# Debug_Phantom_V2.net
KiCad netlist of a schematic drawn in EAGLE
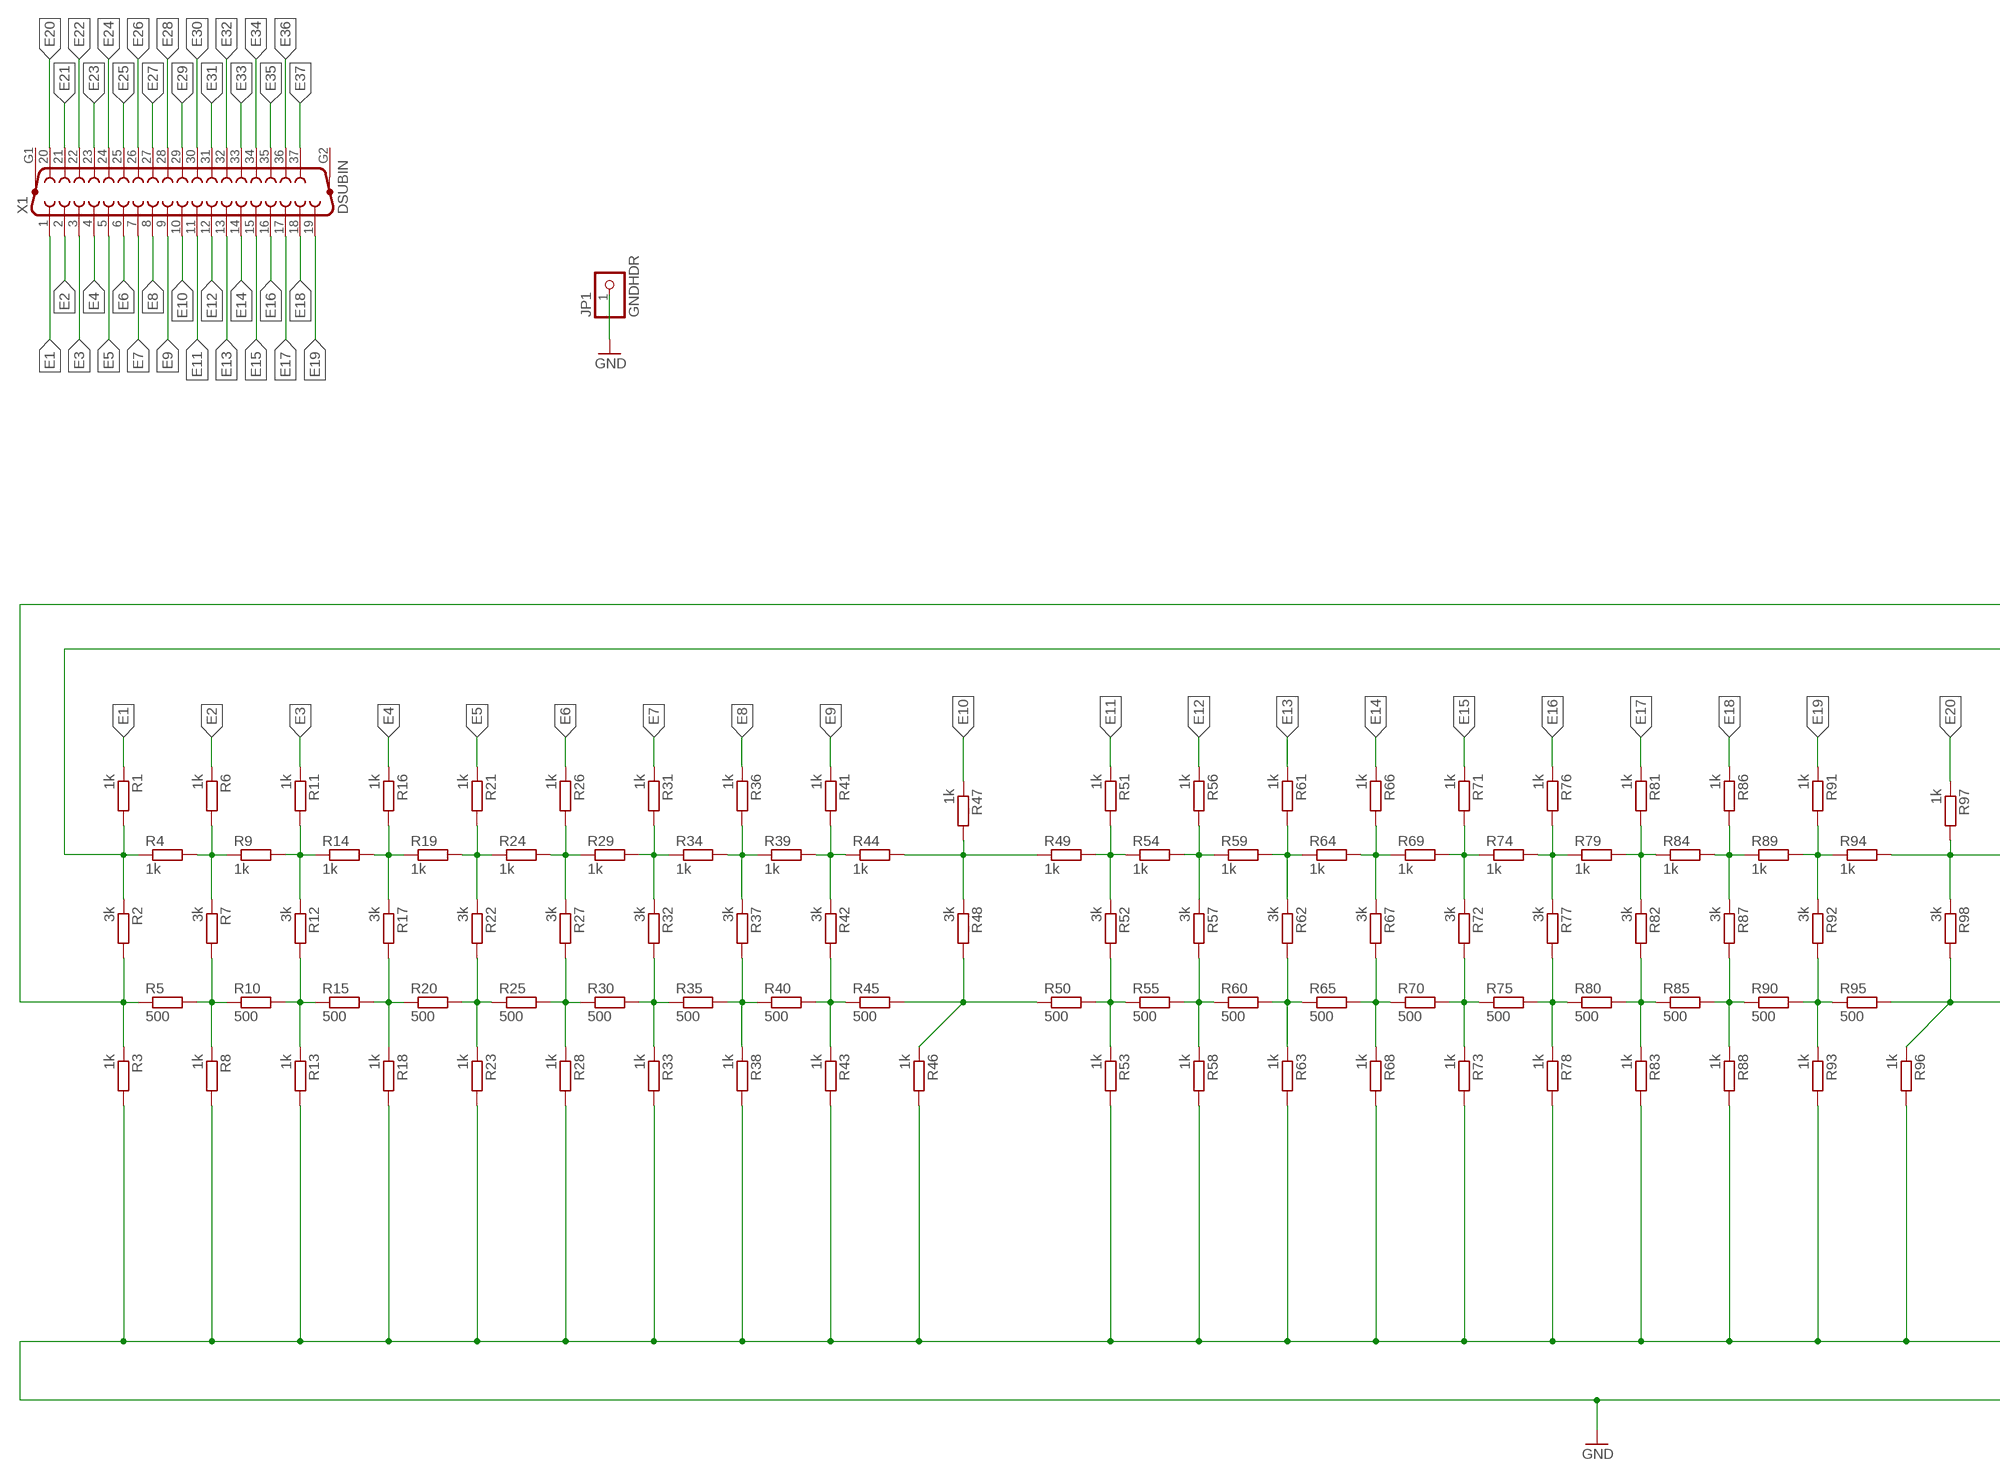
[diagram p0: schematic, sheet 1, part 1 of 2]
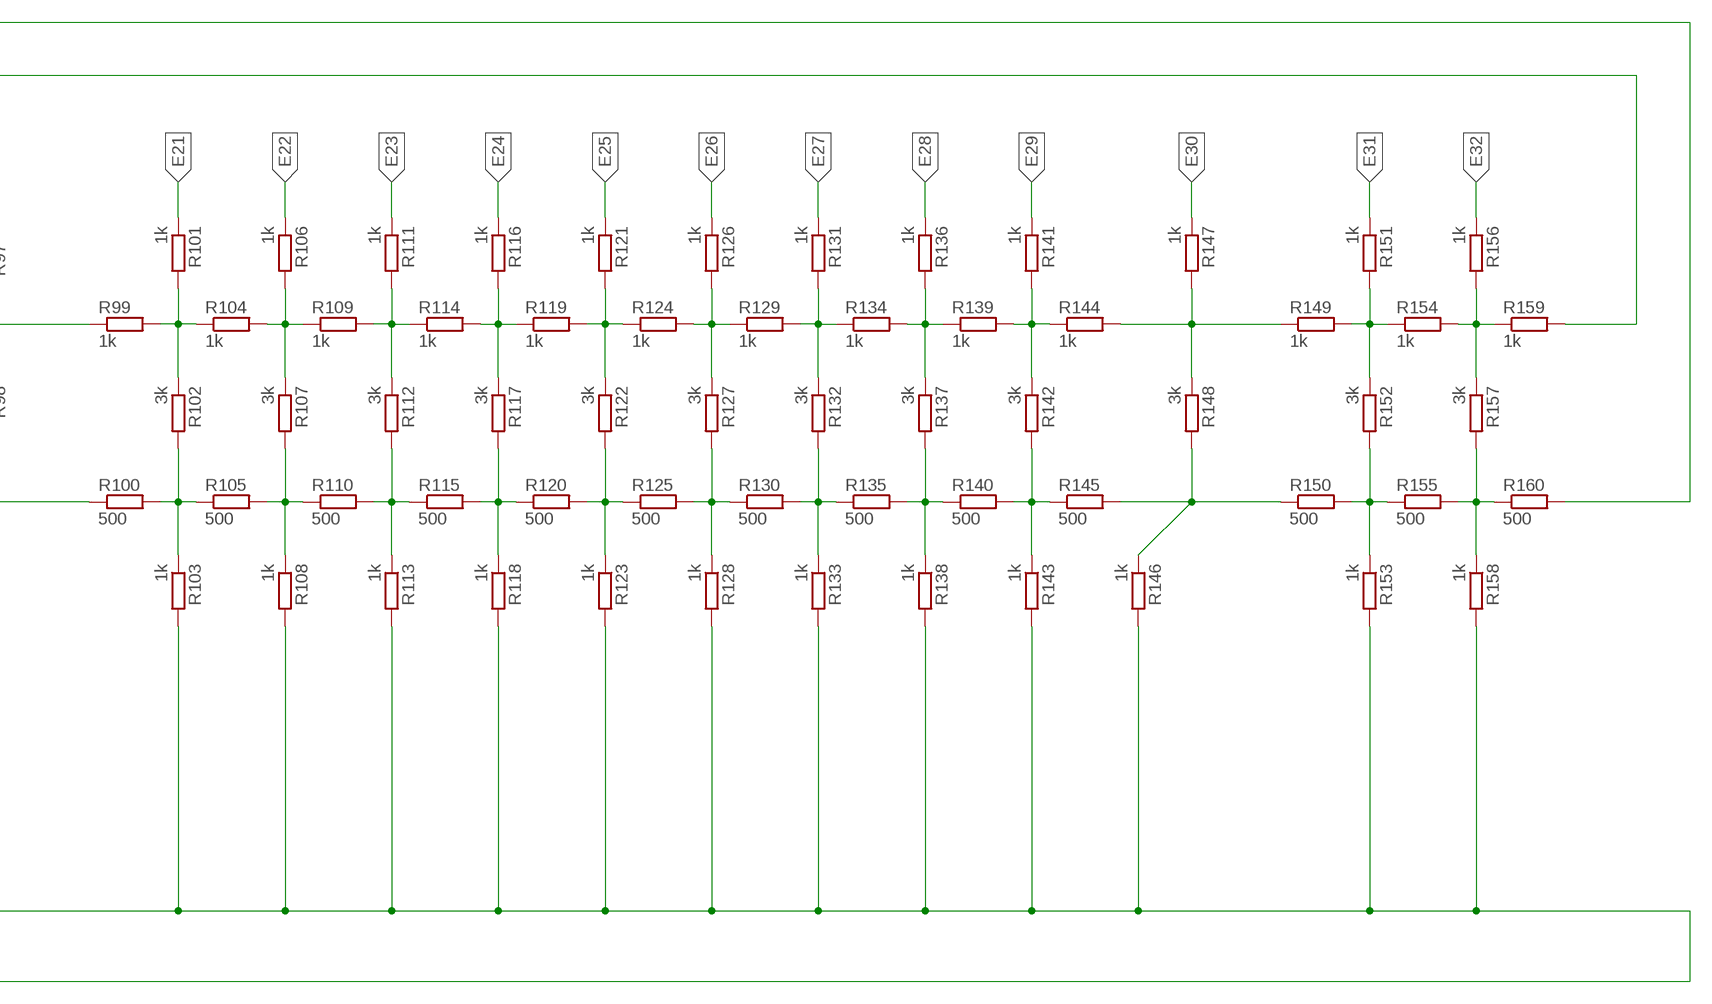
[diagram p1: schematic, sheet 1, part 2 of 2]

(export (version "E")
  (design (tool "Eeschema 10.0.6"))
  (components
    (comp (ref "JP1")
      (value "GNDHDR")
      (footprint "eagle-import:1X01")
      (libsource (lib "eagle-import") (part "PINHD-1X1"))
    )
    (comp (ref "R1")
      (value "1k")
      (footprint "eagle-import:R0402")
      (libsource (lib "eagle-import") (part "R-EU_R0402"))
    )
    (comp (ref "R2")
      (value "3k")
      (footprint "eagle-import:R0402")
      (libsource (lib "eagle-import") (part "R-EU_R0402"))
    )
    (comp (ref "R3")
      (value "1k")
      (footprint "eagle-import:R0402")
      (libsource (lib "eagle-import") (part "R-EU_R0402"))
    )
    (comp (ref "R4")
      (value "1k")
      (footprint "eagle-import:R0402")
      (libsource (lib "eagle-import") (part "R-EU_R0402"))
    )
    (comp (ref "R5")
      (value "500")
      (footprint "eagle-import:R0402")
      (libsource (lib "eagle-import") (part "R-EU_R0402"))
    )
    (comp (ref "R6")
      (value "1k")
      (footprint "eagle-import:R0402")
      (libsource (lib "eagle-import") (part "R-EU_R0402"))
    )
    (comp (ref "R7")
      (value "3k")
      (footprint "eagle-import:R0402")
      (libsource (lib "eagle-import") (part "R-EU_R0402"))
    )
    (comp (ref "R8")
      (value "1k")
      (footprint "eagle-import:R0402")
      (libsource (lib "eagle-import") (part "R-EU_R0402"))
    )
    (comp (ref "R9")
      (value "1k")
      (footprint "eagle-import:R0402")
      (libsource (lib "eagle-import") (part "R-EU_R0402"))
    )
    (comp (ref "R10")
      (value "500")
      (footprint "eagle-import:R0402")
      (libsource (lib "eagle-import") (part "R-EU_R0402"))
    )
    (comp (ref "R11")
      (value "1k")
      (footprint "eagle-import:R0402")
      (libsource (lib "eagle-import") (part "R-EU_R0402"))
    )
    (comp (ref "R12")
      (value "3k")
      (footprint "eagle-import:R0402")
      (libsource (lib "eagle-import") (part "R-EU_R0402"))
    )
    (comp (ref "R13")
      (value "1k")
      (footprint "eagle-import:R0402")
      (libsource (lib "eagle-import") (part "R-EU_R0402"))
    )
    (comp (ref "R14")
      (value "1k")
      (footprint "eagle-import:R0402")
      (libsource (lib "eagle-import") (part "R-EU_R0402"))
    )
    (comp (ref "R15")
      (value "500")
      (footprint "eagle-import:R0402")
      (libsource (lib "eagle-import") (part "R-EU_R0402"))
    )
    (comp (ref "R16")
      (value "1k")
      (footprint "eagle-import:R0402")
      (libsource (lib "eagle-import") (part "R-EU_R0402"))
    )
    (comp (ref "R17")
      (value "3k")
      (footprint "eagle-import:R0402")
      (libsource (lib "eagle-import") (part "R-EU_R0402"))
    )
    (comp (ref "R18")
      (value "1k")
      (footprint "eagle-import:R0402")
      (libsource (lib "eagle-import") (part "R-EU_R0402"))
    )
    (comp (ref "R19")
      (value "1k")
      (footprint "eagle-import:R0402")
      (libsource (lib "eagle-import") (part "R-EU_R0402"))
    )
    (comp (ref "R20")
      (value "500")
      (footprint "eagle-import:R0402")
      (libsource (lib "eagle-import") (part "R-EU_R0402"))
    )
    (comp (ref "R21")
      (value "1k")
      (footprint "eagle-import:R0402")
      (libsource (lib "eagle-import") (part "R-EU_R0402"))
    )
    (comp (ref "R22")
      (value "3k")
      (footprint "eagle-import:R0402")
      (libsource (lib "eagle-import") (part "R-EU_R0402"))
    )
    (comp (ref "R23")
      (value "1k")
      (footprint "eagle-import:R0402")
      (libsource (lib "eagle-import") (part "R-EU_R0402"))
    )
    (comp (ref "R24")
      (value "1k")
      (footprint "eagle-import:R0402")
      (libsource (lib "eagle-import") (part "R-EU_R0402"))
    )
    (comp (ref "R25")
      (value "500")
      (footprint "eagle-import:R0402")
      (libsource (lib "eagle-import") (part "R-EU_R0402"))
    )
    (comp (ref "R26")
      (value "1k")
      (footprint "eagle-import:R0402")
      (libsource (lib "eagle-import") (part "R-EU_R0402"))
    )
    (comp (ref "R27")
      (value "3k")
      (footprint "eagle-import:R0402")
      (libsource (lib "eagle-import") (part "R-EU_R0402"))
    )
    (comp (ref "R28")
      (value "1k")
      (footprint "eagle-import:R0402")
      (libsource (lib "eagle-import") (part "R-EU_R0402"))
    )
    (comp (ref "R29")
      (value "1k")
      (footprint "eagle-import:R0402")
      (libsource (lib "eagle-import") (part "R-EU_R0402"))
    )
    (comp (ref "R30")
      (value "500")
      (footprint "eagle-import:R0402")
      (libsource (lib "eagle-import") (part "R-EU_R0402"))
    )
    (comp (ref "R31")
      (value "1k")
      (footprint "eagle-import:R0402")
      (libsource (lib "eagle-import") (part "R-EU_R0402"))
    )
    (comp (ref "R32")
      (value "3k")
      (footprint "eagle-import:R0402")
      (libsource (lib "eagle-import") (part "R-EU_R0402"))
    )
    (comp (ref "R33")
      (value "1k")
      (footprint "eagle-import:R0402")
      (libsource (lib "eagle-import") (part "R-EU_R0402"))
    )
    (comp (ref "R34")
      (value "1k")
      (footprint "eagle-import:R0402")
      (libsource (lib "eagle-import") (part "R-EU_R0402"))
    )
    (comp (ref "R35")
      (value "500")
      (footprint "eagle-import:R0402")
      (libsource (lib "eagle-import") (part "R-EU_R0402"))
    )
    (comp (ref "R36")
      (value "1k")
      (footprint "eagle-import:R0402")
      (libsource (lib "eagle-import") (part "R-EU_R0402"))
    )
    (comp (ref "R37")
      (value "3k")
      (footprint "eagle-import:R0402")
      (libsource (lib "eagle-import") (part "R-EU_R0402"))
    )
    (comp (ref "R38")
      (value "1k")
      (footprint "eagle-import:R0402")
      (libsource (lib "eagle-import") (part "R-EU_R0402"))
    )
    (comp (ref "R39")
      (value "1k")
      (footprint "eagle-import:R0402")
      (libsource (lib "eagle-import") (part "R-EU_R0402"))
    )
    (comp (ref "R40")
      (value "500")
      (footprint "eagle-import:R0402")
      (libsource (lib "eagle-import") (part "R-EU_R0402"))
    )
    (comp (ref "R41")
      (value "1k")
      (footprint "eagle-import:R0402")
      (libsource (lib "eagle-import") (part "R-EU_R0402"))
    )
    (comp (ref "R42")
      (value "3k")
      (footprint "eagle-import:R0402")
      (libsource (lib "eagle-import") (part "R-EU_R0402"))
    )
    (comp (ref "R43")
      (value "1k")
      (footprint "eagle-import:R0402")
      (libsource (lib "eagle-import") (part "R-EU_R0402"))
    )
    (comp (ref "R44")
      (value "1k")
      (footprint "eagle-import:R0402")
      (libsource (lib "eagle-import") (part "R-EU_R0402"))
    )
    (comp (ref "R45")
      (value "500")
      (footprint "eagle-import:R0402")
      (libsource (lib "eagle-import") (part "R-EU_R0402"))
    )
    (comp (ref "R46")
      (value "1k")
      (footprint "eagle-import:R0402")
      (libsource (lib "eagle-import") (part "R-EU_R0402"))
    )
    (comp (ref "R47")
      (value "1k")
      (footprint "eagle-import:R0402")
      (libsource (lib "eagle-import") (part "R-EU_R0402"))
    )
    (comp (ref "R48")
      (value "3k")
      (footprint "eagle-import:R0402")
      (libsource (lib "eagle-import") (part "R-EU_R0402"))
    )
    (comp (ref "R49")
      (value "1k")
      (footprint "eagle-import:R0402")
      (libsource (lib "eagle-import") (part "R-EU_R0402"))
    )
    (comp (ref "R50")
      (value "500")
      (footprint "eagle-import:R0402")
      (libsource (lib "eagle-import") (part "R-EU_R0402"))
    )
    (comp (ref "R51")
      (value "1k")
      (footprint "eagle-import:R0402")
      (libsource (lib "eagle-import") (part "R-EU_R0402"))
    )
    (comp (ref "R52")
      (value "3k")
      (footprint "eagle-import:R0402")
      (libsource (lib "eagle-import") (part "R-EU_R0402"))
    )
    (comp (ref "R53")
      (value "1k")
      (footprint "eagle-import:R0402")
      (libsource (lib "eagle-import") (part "R-EU_R0402"))
    )
    (comp (ref "R54")
      (value "1k")
      (footprint "eagle-import:R0402")
      (libsource (lib "eagle-import") (part "R-EU_R0402"))
    )
    (comp (ref "R55")
      (value "500")
      (footprint "eagle-import:R0402")
      (libsource (lib "eagle-import") (part "R-EU_R0402"))
    )
    (comp (ref "R56")
      (value "1k")
      (footprint "eagle-import:R0402")
      (libsource (lib "eagle-import") (part "R-EU_R0402"))
    )
    (comp (ref "R57")
      (value "3k")
      (footprint "eagle-import:R0402")
      (libsource (lib "eagle-import") (part "R-EU_R0402"))
    )
    (comp (ref "R58")
      (value "1k")
      (footprint "eagle-import:R0402")
      (libsource (lib "eagle-import") (part "R-EU_R0402"))
    )
    (comp (ref "R59")
      (value "1k")
      (footprint "eagle-import:R0402")
      (libsource (lib "eagle-import") (part "R-EU_R0402"))
    )
    (comp (ref "R60")
      (value "500")
      (footprint "eagle-import:R0402")
      (libsource (lib "eagle-import") (part "R-EU_R0402"))
    )
    (comp (ref "R61")
      (value "1k")
      (footprint "eagle-import:R0402")
      (libsource (lib "eagle-import") (part "R-EU_R0402"))
    )
    (comp (ref "R62")
      (value "3k")
      (footprint "eagle-import:R0402")
      (libsource (lib "eagle-import") (part "R-EU_R0402"))
    )
    (comp (ref "R63")
      (value "1k")
      (footprint "eagle-import:R0402")
      (libsource (lib "eagle-import") (part "R-EU_R0402"))
    )
    (comp (ref "R64")
      (value "1k")
      (footprint "eagle-import:R0402")
      (libsource (lib "eagle-import") (part "R-EU_R0402"))
    )
    (comp (ref "R65")
      (value "500")
      (footprint "eagle-import:R0402")
      (libsource (lib "eagle-import") (part "R-EU_R0402"))
    )
    (comp (ref "R66")
      (value "1k")
      (footprint "eagle-import:R0402")
      (libsource (lib "eagle-import") (part "R-EU_R0402"))
    )
    (comp (ref "R67")
      (value "3k")
      (footprint "eagle-import:R0402")
      (libsource (lib "eagle-import") (part "R-EU_R0402"))
    )
    (comp (ref "R68")
      (value "1k")
      (footprint "eagle-import:R0402")
      (libsource (lib "eagle-import") (part "R-EU_R0402"))
    )
    (comp (ref "R69")
      (value "1k")
      (footprint "eagle-import:R0402")
      (libsource (lib "eagle-import") (part "R-EU_R0402"))
    )
    (comp (ref "R70")
      (value "500")
      (footprint "eagle-import:R0402")
      (libsource (lib "eagle-import") (part "R-EU_R0402"))
    )
    (comp (ref "R71")
      (value "1k")
      (footprint "eagle-import:R0402")
      (libsource (lib "eagle-import") (part "R-EU_R0402"))
    )
    (comp (ref "R72")
      (value "3k")
      (footprint "eagle-import:R0402")
      (libsource (lib "eagle-import") (part "R-EU_R0402"))
    )
    (comp (ref "R73")
      (value "1k")
      (footprint "eagle-import:R0402")
      (libsource (lib "eagle-import") (part "R-EU_R0402"))
    )
    (comp (ref "R74")
      (value "1k")
      (footprint "eagle-import:R0402")
      (libsource (lib "eagle-import") (part "R-EU_R0402"))
    )
    (comp (ref "R75")
      (value "500")
      (footprint "eagle-import:R0402")
      (libsource (lib "eagle-import") (part "R-EU_R0402"))
    )
    (comp (ref "R76")
      (value "1k")
      (footprint "eagle-import:R0402")
      (libsource (lib "eagle-import") (part "R-EU_R0402"))
    )
    (comp (ref "R77")
      (value "3k")
      (footprint "eagle-import:R0402")
      (libsource (lib "eagle-import") (part "R-EU_R0402"))
    )
    (comp (ref "R78")
      (value "1k")
      (footprint "eagle-import:R0402")
      (libsource (lib "eagle-import") (part "R-EU_R0402"))
    )
    (comp (ref "R79")
      (value "1k")
      (footprint "eagle-import:R0402")
      (libsource (lib "eagle-import") (part "R-EU_R0402"))
    )
    (comp (ref "R80")
      (value "500")
      (footprint "eagle-import:R0402")
      (libsource (lib "eagle-import") (part "R-EU_R0402"))
    )
    (comp (ref "R81")
      (value "1k")
      (footprint "eagle-import:R0402")
      (libsource (lib "eagle-import") (part "R-EU_R0402"))
    )
    (comp (ref "R82")
      (value "3k")
      (footprint "eagle-import:R0402")
      (libsource (lib "eagle-import") (part "R-EU_R0402"))
    )
    (comp (ref "R83")
      (value "1k")
      (footprint "eagle-import:R0402")
      (libsource (lib "eagle-import") (part "R-EU_R0402"))
    )
    (comp (ref "R84")
      (value "1k")
      (footprint "eagle-import:R0402")
      (libsource (lib "eagle-import") (part "R-EU_R0402"))
    )
    (comp (ref "R85")
      (value "500")
      (footprint "eagle-import:R0402")
      (libsource (lib "eagle-import") (part "R-EU_R0402"))
    )
    (comp (ref "R86")
      (value "1k")
      (footprint "eagle-import:R0402")
      (libsource (lib "eagle-import") (part "R-EU_R0402"))
    )
    (comp (ref "R87")
      (value "3k")
      (footprint "eagle-import:R0402")
      (libsource (lib "eagle-import") (part "R-EU_R0402"))
    )
    (comp (ref "R88")
      (value "1k")
      (footprint "eagle-import:R0402")
      (libsource (lib "eagle-import") (part "R-EU_R0402"))
    )
    (comp (ref "R89")
      (value "1k")
      (footprint "eagle-import:R0402")
      (libsource (lib "eagle-import") (part "R-EU_R0402"))
    )
    (comp (ref "R90")
      (value "500")
      (footprint "eagle-import:R0402")
      (libsource (lib "eagle-import") (part "R-EU_R0402"))
    )
    (comp (ref "R91")
      (value "1k")
      (footprint "eagle-import:R0402")
      (libsource (lib "eagle-import") (part "R-EU_R0402"))
    )
    (comp (ref "R92")
      (value "3k")
      (footprint "eagle-import:R0402")
      (libsource (lib "eagle-import") (part "R-EU_R0402"))
    )
    (comp (ref "R93")
      (value "1k")
      (footprint "eagle-import:R0402")
      (libsource (lib "eagle-import") (part "R-EU_R0402"))
    )
    (comp (ref "R94")
      (value "1k")
      (footprint "eagle-import:R0402")
      (libsource (lib "eagle-import") (part "R-EU_R0402"))
    )
    (comp (ref "R95")
      (value "500")
      (footprint "eagle-import:R0402")
      (libsource (lib "eagle-import") (part "R-EU_R0402"))
    )
    (comp (ref "R96")
      (value "1k")
      (footprint "eagle-import:R0402")
      (libsource (lib "eagle-import") (part "R-EU_R0402"))
    )
    (comp (ref "R97")
      (value "1k")
      (footprint "eagle-import:R0402")
      (libsource (lib "eagle-import") (part "R-EU_R0402"))
    )
    (comp (ref "R98")
      (value "3k")
      (footprint "eagle-import:R0402")
      (libsource (lib "eagle-import") (part "R-EU_R0402"))
    )
    (comp (ref "R99")
      (value "1k")
      (footprint "eagle-import:R0402")
      (libsource (lib "eagle-import") (part "R-EU_R0402"))
    )
    (comp (ref "R100")
      (value "500")
      (footprint "eagle-import:R0402")
      (libsource (lib "eagle-import") (part "R-EU_R0402"))
    )
    (comp (ref "R101")
      (value "1k")
      (footprint "eagle-import:R0402")
      (libsource (lib "eagle-import") (part "R-EU_R0402"))
    )
    (comp (ref "R102")
      (value "3k")
      (footprint "eagle-import:R0402")
      (libsource (lib "eagle-import") (part "R-EU_R0402"))
    )
    (comp (ref "R103")
      (value "1k")
      (footprint "eagle-import:R0402")
      (libsource (lib "eagle-import") (part "R-EU_R0402"))
    )
    (comp (ref "R104")
      (value "1k")
      (footprint "eagle-import:R0402")
      (libsource (lib "eagle-import") (part "R-EU_R0402"))
    )
    (comp (ref "R105")
      (value "500")
      (footprint "eagle-import:R0402")
      (libsource (lib "eagle-import") (part "R-EU_R0402"))
    )
    (comp (ref "R106")
      (value "1k")
      (footprint "eagle-import:R0402")
      (libsource (lib "eagle-import") (part "R-EU_R0402"))
    )
    (comp (ref "R107")
      (value "3k")
      (footprint "eagle-import:R0402")
      (libsource (lib "eagle-import") (part "R-EU_R0402"))
    )
    (comp (ref "R108")
      (value "1k")
      (footprint "eagle-import:R0402")
      (libsource (lib "eagle-import") (part "R-EU_R0402"))
    )
    (comp (ref "R109")
      (value "1k")
      (footprint "eagle-import:R0402")
      (libsource (lib "eagle-import") (part "R-EU_R0402"))
    )
    (comp (ref "R110")
      (value "500")
      (footprint "eagle-import:R0402")
      (libsource (lib "eagle-import") (part "R-EU_R0402"))
    )
    (comp (ref "R111")
      (value "1k")
      (footprint "eagle-import:R0402")
      (libsource (lib "eagle-import") (part "R-EU_R0402"))
    )
    (comp (ref "R112")
      (value "3k")
      (footprint "eagle-import:R0402")
      (libsource (lib "eagle-import") (part "R-EU_R0402"))
    )
    (comp (ref "R113")
      (value "1k")
      (footprint "eagle-import:R0402")
      (libsource (lib "eagle-import") (part "R-EU_R0402"))
    )
    (comp (ref "R114")
      (value "1k")
      (footprint "eagle-import:R0402")
      (libsource (lib "eagle-import") (part "R-EU_R0402"))
    )
    (comp (ref "R115")
      (value "500")
      (footprint "eagle-import:R0402")
      (libsource (lib "eagle-import") (part "R-EU_R0402"))
    )
    (comp (ref "R116")
      (value "1k")
      (footprint "eagle-import:R0402")
      (libsource (lib "eagle-import") (part "R-EU_R0402"))
    )
    (comp (ref "R117")
      (value "3k")
      (footprint "eagle-import:R0402")
      (libsource (lib "eagle-import") (part "R-EU_R0402"))
    )
    (comp (ref "R118")
      (value "1k")
      (footprint "eagle-import:R0402")
      (libsource (lib "eagle-import") (part "R-EU_R0402"))
    )
    (comp (ref "R119")
      (value "1k")
      (footprint "eagle-import:R0402")
      (libsource (lib "eagle-import") (part "R-EU_R0402"))
    )
    (comp (ref "R120")
      (value "500")
      (footprint "eagle-import:R0402")
      (libsource (lib "eagle-import") (part "R-EU_R0402"))
    )
    (comp (ref "R121")
      (value "1k")
      (footprint "eagle-import:R0402")
      (libsource (lib "eagle-import") (part "R-EU_R0402"))
    )
    (comp (ref "R122")
      (value "3k")
      (footprint "eagle-import:R0402")
      (libsource (lib "eagle-import") (part "R-EU_R0402"))
    )
    (comp (ref "R123")
      (value "1k")
      (footprint "eagle-import:R0402")
      (libsource (lib "eagle-import") (part "R-EU_R0402"))
    )
    (comp (ref "R124")
      (value "1k")
      (footprint "eagle-import:R0402")
      (libsource (lib "eagle-import") (part "R-EU_R0402"))
    )
    (comp (ref "R125")
      (value "500")
      (footprint "eagle-import:R0402")
      (libsource (lib "eagle-import") (part "R-EU_R0402"))
    )
    (comp (ref "R126")
      (value "1k")
      (footprint "eagle-import:R0402")
      (libsource (lib "eagle-import") (part "R-EU_R0402"))
    )
    (comp (ref "R127")
      (value "3k")
      (footprint "eagle-import:R0402")
      (libsource (lib "eagle-import") (part "R-EU_R0402"))
    )
    (comp (ref "R128")
      (value "1k")
      (footprint "eagle-import:R0402")
      (libsource (lib "eagle-import") (part "R-EU_R0402"))
    )
    (comp (ref "R129")
      (value "1k")
      (footprint "eagle-import:R0402")
      (libsource (lib "eagle-import") (part "R-EU_R0402"))
    )
    (comp (ref "R130")
      (value "500")
      (footprint "eagle-import:R0402")
      (libsource (lib "eagle-import") (part "R-EU_R0402"))
    )
    (comp (ref "R131")
      (value "1k")
      (footprint "eagle-import:R0402")
      (libsource (lib "eagle-import") (part "R-EU_R0402"))
    )
    (comp (ref "R132")
      (value "3k")
      (footprint "eagle-import:R0402")
      (libsource (lib "eagle-import") (part "R-EU_R0402"))
    )
    (comp (ref "R133")
      (value "1k")
      (footprint "eagle-import:R0402")
      (libsource (lib "eagle-import") (part "R-EU_R0402"))
    )
    (comp (ref "R134")
      (value "1k")
      (footprint "eagle-import:R0402")
      (libsource (lib "eagle-import") (part "R-EU_R0402"))
    )
    (comp (ref "R135")
      (value "500")
      (footprint "eagle-import:R0402")
      (libsource (lib "eagle-import") (part "R-EU_R0402"))
    )
    (comp (ref "R136")
      (value "1k")
      (footprint "eagle-import:R0402")
      (libsource (lib "eagle-import") (part "R-EU_R0402"))
    )
    (comp (ref "R137")
      (value "3k")
      (footprint "eagle-import:R0402")
      (libsource (lib "eagle-import") (part "R-EU_R0402"))
    )
    (comp (ref "R138")
      (value "1k")
      (footprint "eagle-import:R0402")
      (libsource (lib "eagle-import") (part "R-EU_R0402"))
    )
    (comp (ref "R139")
      (value "1k")
      (footprint "eagle-import:R0402")
      (libsource (lib "eagle-import") (part "R-EU_R0402"))
    )
    (comp (ref "R140")
      (value "500")
      (footprint "eagle-import:R0402")
      (libsource (lib "eagle-import") (part "R-EU_R0402"))
    )
    (comp (ref "R141")
      (value "1k")
      (footprint "eagle-import:R0402")
      (libsource (lib "eagle-import") (part "R-EU_R0402"))
    )
    (comp (ref "R142")
      (value "3k")
      (footprint "eagle-import:R0402")
      (libsource (lib "eagle-import") (part "R-EU_R0402"))
    )
    (comp (ref "R143")
      (value "1k")
      (footprint "eagle-import:R0402")
      (libsource (lib "eagle-import") (part "R-EU_R0402"))
    )
    (comp (ref "R144")
      (value "1k")
      (footprint "eagle-import:R0402")
      (libsource (lib "eagle-import") (part "R-EU_R0402"))
    )
    (comp (ref "R145")
      (value "500")
      (footprint "eagle-import:R0402")
      (libsource (lib "eagle-import") (part "R-EU_R0402"))
    )
    (comp (ref "R146")
      (value "1k")
      (footprint "eagle-import:R0402")
      (libsource (lib "eagle-import") (part "R-EU_R0402"))
    )
    (comp (ref "R147")
      (value "1k")
      (footprint "eagle-import:R0402")
      (libsource (lib "eagle-import") (part "R-EU_R0402"))
    )
    (comp (ref "R148")
      (value "3k")
      (footprint "eagle-import:R0402")
      (libsource (lib "eagle-import") (part "R-EU_R0402"))
    )
    (comp (ref "R149")
      (value "1k")
      (footprint "eagle-import:R0402")
      (libsource (lib "eagle-import") (part "R-EU_R0402"))
    )
    (comp (ref "R150")
      (value "500")
      (footprint "eagle-import:R0402")
      (libsource (lib "eagle-import") (part "R-EU_R0402"))
    )
    (comp (ref "R151")
      (value "1k")
      (footprint "eagle-import:R0402")
      (libsource (lib "eagle-import") (part "R-EU_R0402"))
    )
    (comp (ref "R152")
      (value "3k")
      (footprint "eagle-import:R0402")
      (libsource (lib "eagle-import") (part "R-EU_R0402"))
    )
    (comp (ref "R153")
      (value "1k")
      (footprint "eagle-import:R0402")
      (libsource (lib "eagle-import") (part "R-EU_R0402"))
    )
    (comp (ref "R154")
      (value "1k")
      (footprint "eagle-import:R0402")
      (libsource (lib "eagle-import") (part "R-EU_R0402"))
    )
    (comp (ref "R155")
      (value "500")
      (footprint "eagle-import:R0402")
      (libsource (lib "eagle-import") (part "R-EU_R0402"))
    )
    (comp (ref "R156")
      (value "1k")
      (footprint "eagle-import:R0402")
      (libsource (lib "eagle-import") (part "R-EU_R0402"))
    )
    (comp (ref "R157")
      (value "3k")
      (footprint "eagle-import:R0402")
      (libsource (lib "eagle-import") (part "R-EU_R0402"))
    )
    (comp (ref "R158")
      (value "1k")
      (footprint "eagle-import:R0402")
      (libsource (lib "eagle-import") (part "R-EU_R0402"))
    )
    (comp (ref "R159")
      (value "1k")
      (footprint "eagle-import:R0402")
      (libsource (lib "eagle-import") (part "R-EU_R0402"))
    )
    (comp (ref "R160")
      (value "500")
      (footprint "eagle-import:R0402")
      (libsource (lib "eagle-import") (part "R-EU_R0402"))
    )
    (comp (ref "X1")
      (value "DSUBIN")
      (footprint "eagle-import:F37VP")
      (libsource (lib "eagle-import") (part "F37VP"))
    )
  )
  (nets
    (net (code "1") (name "E1") (class "Default")
      (node (ref "R1") (pin "1") (pinfunction "1_1") (pintype "passive"))
      (node (ref "X1") (pin "1") (pinfunction "1_1") (pintype "passive"))
    )
    (net (code "2") (name "E2") (class "Default")
      (node (ref "R6") (pin "1") (pinfunction "1_1") (pintype "passive"))
      (node (ref "X1") (pin "2") (pinfunction "2_2") (pintype "passive"))
    )
    (net (code "3") (name "E3") (class "Default")
      (node (ref "R11") (pin "1") (pinfunction "1_1") (pintype "passive"))
      (node (ref "X1") (pin "3") (pinfunction "3_3") (pintype "passive"))
    )
    (net (code "4") (name "E4") (class "Default")
      (node (ref "R16") (pin "1") (pinfunction "1_1") (pintype "passive"))
      (node (ref "X1") (pin "4") (pinfunction "4_4") (pintype "passive"))
    )
    (net (code "5") (name "E5") (class "Default")
      (node (ref "R21") (pin "1") (pinfunction "1_1") (pintype "passive"))
      (node (ref "X1") (pin "5") (pinfunction "5_5") (pintype "passive"))
    )
    (net (code "6") (name "E6") (class "Default")
      (node (ref "R26") (pin "1") (pinfunction "1_1") (pintype "passive"))
      (node (ref "X1") (pin "6") (pinfunction "6_6") (pintype "passive"))
    )
    (net (code "7") (name "E7") (class "Default")
      (node (ref "R31") (pin "1") (pinfunction "1_1") (pintype "passive"))
      (node (ref "X1") (pin "7") (pinfunction "7_7") (pintype "passive"))
    )
    (net (code "8") (name "E8") (class "Default")
      (node (ref "R36") (pin "1") (pinfunction "1_1") (pintype "passive"))
      (node (ref "X1") (pin "8") (pinfunction "8_8") (pintype "passive"))
    )
    (net (code "9") (name "E9") (class "Default")
      (node (ref "R41") (pin "1") (pinfunction "1_1") (pintype "passive"))
      (node (ref "X1") (pin "9") (pinfunction "9_9") (pintype "passive"))
    )
    (net (code "10") (name "E10") (class "Default")
      (node (ref "R47") (pin "1") (pinfunction "1_1") (pintype "passive"))
      (node (ref "X1") (pin "10") (pinfunction "10_10") (pintype "passive"))
    )
    (net (code "11") (name "E11") (class "Default")
      (node (ref "R51") (pin "1") (pinfunction "1_1") (pintype "passive"))
      (node (ref "X1") (pin "11") (pinfunction "11_11") (pintype "passive"))
    )
    (net (code "12") (name "E12") (class "Default")
      (node (ref "R56") (pin "1") (pinfunction "1_1") (pintype "passive"))
      (node (ref "X1") (pin "12") (pinfunction "12_12") (pintype "passive"))
    )
    (net (code "13") (name "E13") (class "Default")
      (node (ref "R61") (pin "1") (pinfunction "1_1") (pintype "passive"))
      (node (ref "X1") (pin "13") (pinfunction "13_13") (pintype "passive"))
    )
    (net (code "14") (name "E14") (class "Default")
      (node (ref "R66") (pin "1") (pinfunction "1_1") (pintype "passive"))
      (node (ref "X1") (pin "14") (pinfunction "14_14") (pintype "passive"))
    )
    (net (code "15") (name "E15") (class "Default")
      (node (ref "R71") (pin "1") (pinfunction "1_1") (pintype "passive"))
      (node (ref "X1") (pin "15") (pinfunction "15_15") (pintype "passive"))
    )
    (net (code "16") (name "E16") (class "Default")
      (node (ref "R76") (pin "1") (pinfunction "1_1") (pintype "passive"))
      (node (ref "X1") (pin "16") (pinfunction "16_16") (pintype "passive"))
    )
    (net (code "17") (name "E17") (class "Default")
      (node (ref "R81") (pin "1") (pinfunction "1_1") (pintype "passive"))
      (node (ref "X1") (pin "17") (pinfunction "17_17") (pintype "passive"))
    )
    (net (code "18") (name "E18") (class "Default")
      (node (ref "R86") (pin "1") (pinfunction "1_1") (pintype "passive"))
      (node (ref "X1") (pin "18") (pinfunction "18_18") (pintype "passive"))
    )
    (net (code "19") (name "E19") (class "Default")
      (node (ref "R91") (pin "1") (pinfunction "1_1") (pintype "passive"))
      (node (ref "X1") (pin "19") (pinfunction "19_19") (pintype "passive"))
    )
    (net (code "20") (name "E20") (class "Default")
      (node (ref "R97") (pin "1") (pinfunction "1_1") (pintype "passive"))
      (node (ref "X1") (pin "20") (pinfunction "20_20") (pintype "passive"))
    )
    (net (code "21") (name "E21") (class "Default")
      (node (ref "R101") (pin "1") (pinfunction "1_1") (pintype "passive"))
      (node (ref "X1") (pin "21") (pinfunction "21_21") (pintype "passive"))
    )
    (net (code "22") (name "E22") (class "Default")
      (node (ref "R106") (pin "1") (pinfunction "1_1") (pintype "passive"))
      (node (ref "X1") (pin "22") (pinfunction "22_22") (pintype "passive"))
    )
    (net (code "23") (name "E23") (class "Default")
      (node (ref "R111") (pin "1") (pinfunction "1_1") (pintype "passive"))
      (node (ref "X1") (pin "23") (pinfunction "23_23") (pintype "passive"))
    )
    (net (code "24") (name "E24") (class "Default")
      (node (ref "R116") (pin "1") (pinfunction "1_1") (pintype "passive"))
      (node (ref "X1") (pin "24") (pinfunction "24_24") (pintype "passive"))
    )
    (net (code "25") (name "E25") (class "Default")
      (node (ref "R121") (pin "1") (pinfunction "1_1") (pintype "passive"))
      (node (ref "X1") (pin "25") (pinfunction "25_25") (pintype "passive"))
    )
    (net (code "26") (name "E26") (class "Default")
      (node (ref "R126") (pin "1") (pinfunction "1_1") (pintype "passive"))
      (node (ref "X1") (pin "26") (pinfunction "26_26") (pintype "passive"))
    )
    (net (code "27") (name "E27") (class "Default")
      (node (ref "R131") (pin "1") (pinfunction "1_1") (pintype "passive"))
      (node (ref "X1") (pin "27") (pinfunction "27_27") (pintype "passive"))
    )
    (net (code "28") (name "E28") (class "Default")
      (node (ref "R136") (pin "1") (pinfunction "1_1") (pintype "passive"))
      (node (ref "X1") (pin "28") (pinfunction "28_28") (pintype "passive"))
    )
    (net (code "29") (name "E29") (class "Default")
      (node (ref "R141") (pin "1") (pinfunction "1_1") (pintype "passive"))
      (node (ref "X1") (pin "29") (pinfunction "29_29") (pintype "passive"))
    )
    (net (code "30") (name "E30") (class "Default")
      (node (ref "R147") (pin "1") (pinfunction "1_1") (pintype "passive"))
      (node (ref "X1") (pin "30") (pinfunction "30_30") (pintype "passive"))
    )
    (net (code "31") (name "E31") (class "Default")
      (node (ref "R151") (pin "1") (pinfunction "1_1") (pintype "passive"))
      (node (ref "X1") (pin "31") (pinfunction "31_31") (pintype "passive"))
    )
    (net (code "32") (name "E32") (class "Default")
      (node (ref "R156") (pin "1") (pinfunction "1_1") (pintype "passive"))
      (node (ref "X1") (pin "32") (pinfunction "32_32") (pintype "passive"))
    )
    (net (code "33") (name "E33") (class "Default")
      (node (ref "X1") (pin "33") (pinfunction "33_33") (pintype "passive"))
    )
    (net (code "34") (name "E34") (class "Default")
      (node (ref "X1") (pin "34") (pinfunction "34_34") (pintype "passive"))
    )
    (net (code "35") (name "E35") (class "Default")
      (node (ref "X1") (pin "35") (pinfunction "35_35") (pintype "passive"))
    )
    (net (code "36") (name "E36") (class "Default")
      (node (ref "X1") (pin "36") (pinfunction "36_36") (pintype "passive"))
    )
    (net (code "37") (name "E37") (class "Default")
      (node (ref "X1") (pin "37") (pinfunction "37_37") (pintype "passive"))
    )
    (net (code "38") (name "GND") (class "Default")
      (node (ref "JP1") (pin "1") (pinfunction "1_1") (pintype "passive"))
      (node (ref "R103") (pin "2") (pinfunction "2_2") (pintype "passive"))
      (node (ref "R108") (pin "2") (pinfunction "2_2") (pintype "passive"))
      (node (ref "R113") (pin "2") (pinfunction "2_2") (pintype "passive"))
      (node (ref "R118") (pin "2") (pinfunction "2_2") (pintype "passive"))
      (node (ref "R123") (pin "2") (pinfunction "2_2") (pintype "passive"))
      (node (ref "R128") (pin "2") (pinfunction "2_2") (pintype "passive"))
      (node (ref "R13") (pin "2") (pinfunction "2_2") (pintype "passive"))
      (node (ref "R133") (pin "2") (pinfunction "2_2") (pintype "passive"))
      (node (ref "R138") (pin "2") (pinfunction "2_2") (pintype "passive"))
      (node (ref "R143") (pin "2") (pinfunction "2_2") (pintype "passive"))
      (node (ref "R146") (pin "2") (pinfunction "2_2") (pintype "passive"))
      (node (ref "R153") (pin "2") (pinfunction "2_2") (pintype "passive"))
      (node (ref "R158") (pin "2") (pinfunction "2_2") (pintype "passive"))
      (node (ref "R18") (pin "2") (pinfunction "2_2") (pintype "passive"))
      (node (ref "R23") (pin "2") (pinfunction "2_2") (pintype "passive"))
      (node (ref "R28") (pin "2") (pinfunction "2_2") (pintype "passive"))
      (node (ref "R3") (pin "2") (pinfunction "2_2") (pintype "passive"))
      (node (ref "R33") (pin "2") (pinfunction "2_2") (pintype "passive"))
      (node (ref "R38") (pin "2") (pinfunction "2_2") (pintype "passive"))
      (node (ref "R43") (pin "2") (pinfunction "2_2") (pintype "passive"))
      (node (ref "R46") (pin "2") (pinfunction "2_2") (pintype "passive"))
      (node (ref "R53") (pin "2") (pinfunction "2_2") (pintype "passive"))
      (node (ref "R58") (pin "2") (pinfunction "2_2") (pintype "passive"))
      (node (ref "R63") (pin "2") (pinfunction "2_2") (pintype "passive"))
      (node (ref "R68") (pin "2") (pinfunction "2_2") (pintype "passive"))
      (node (ref "R73") (pin "2") (pinfunction "2_2") (pintype "passive"))
      (node (ref "R78") (pin "2") (pinfunction "2_2") (pintype "passive"))
      (node (ref "R8") (pin "2") (pinfunction "2_2") (pintype "passive"))
      (node (ref "R83") (pin "2") (pinfunction "2_2") (pintype "passive"))
      (node (ref "R88") (pin "2") (pinfunction "2_2") (pintype "passive"))
      (node (ref "R93") (pin "2") (pinfunction "2_2") (pintype "passive"))
      (node (ref "R96") (pin "2") (pinfunction "2_2") (pintype "passive"))
    )
    (net (code "39") (name "Net-(R1-Pad2)") (class "Default")
      (node (ref "R1") (pin "2") (pinfunction "2_2") (pintype "passive"))
      (node (ref "R159") (pin "2") (pinfunction "2_2") (pintype "passive"))
      (node (ref "R2") (pin "1") (pinfunction "1_1") (pintype "passive"))
      (node (ref "R4") (pin "1") (pinfunction "1_1") (pintype "passive"))
    )
    (net (code "40") (name "Net-(R4-Pad2)") (class "Default")
      (node (ref "R4") (pin "2") (pinfunction "2_2") (pintype "passive"))
      (node (ref "R6") (pin "2") (pinfunction "2_2") (pintype "passive"))
      (node (ref "R7") (pin "1") (pinfunction "1_1") (pintype "passive"))
      (node (ref "R9") (pin "1") (pinfunction "1_1") (pintype "passive"))
    )
    (net (code "41") (name "Net-(R10-Pad1)") (class "Default")
      (node (ref "R10") (pin "1") (pinfunction "1_1") (pintype "passive"))
      (node (ref "R5") (pin "2") (pinfunction "2_2") (pintype "passive"))
      (node (ref "R7") (pin "2") (pinfunction "2_2") (pintype "passive"))
      (node (ref "R8") (pin "1") (pinfunction "1_1") (pintype "passive"))
    )
    (net (code "42") (name "Net-(R10-Pad2)") (class "Default")
      (node (ref "R10") (pin "2") (pinfunction "2_2") (pintype "passive"))
      (node (ref "R12") (pin "2") (pinfunction "2_2") (pintype "passive"))
      (node (ref "R13") (pin "1") (pinfunction "1_1") (pintype "passive"))
      (node (ref "R15") (pin "1") (pinfunction "1_1") (pintype "passive"))
    )
    (net (code "43") (name "Net-(R11-Pad2)") (class "Default")
      (node (ref "R11") (pin "2") (pinfunction "2_2") (pintype "passive"))
      (node (ref "R12") (pin "1") (pinfunction "1_1") (pintype "passive"))
      (node (ref "R14") (pin "1") (pinfunction "1_1") (pintype "passive"))
      (node (ref "R9") (pin "2") (pinfunction "2_2") (pintype "passive"))
    )
    (net (code "44") (name "Net-(R14-Pad2)") (class "Default")
      (node (ref "R14") (pin "2") (pinfunction "2_2") (pintype "passive"))
      (node (ref "R16") (pin "2") (pinfunction "2_2") (pintype "passive"))
      (node (ref "R17") (pin "1") (pinfunction "1_1") (pintype "passive"))
      (node (ref "R19") (pin "1") (pinfunction "1_1") (pintype "passive"))
    )
    (net (code "45") (name "Net-(R15-Pad2)") (class "Default")
      (node (ref "R15") (pin "2") (pinfunction "2_2") (pintype "passive"))
      (node (ref "R17") (pin "2") (pinfunction "2_2") (pintype "passive"))
      (node (ref "R18") (pin "1") (pinfunction "1_1") (pintype "passive"))
      (node (ref "R20") (pin "1") (pinfunction "1_1") (pintype "passive"))
    )
    (net (code "46") (name "Net-(R19-Pad2)") (class "Default")
      (node (ref "R19") (pin "2") (pinfunction "2_2") (pintype "passive"))
      (node (ref "R21") (pin "2") (pinfunction "2_2") (pintype "passive"))
      (node (ref "R22") (pin "1") (pinfunction "1_1") (pintype "passive"))
      (node (ref "R24") (pin "1") (pinfunction "1_1") (pintype "passive"))
    )
    (net (code "47") (name "Net-(R20-Pad2)") (class "Default")
      (node (ref "R20") (pin "2") (pinfunction "2_2") (pintype "passive"))
      (node (ref "R22") (pin "2") (pinfunction "2_2") (pintype "passive"))
      (node (ref "R23") (pin "1") (pinfunction "1_1") (pintype "passive"))
      (node (ref "R25") (pin "1") (pinfunction "1_1") (pintype "passive"))
    )
    (net (code "48") (name "Net-(R24-Pad2)") (class "Default")
      (node (ref "R24") (pin "2") (pinfunction "2_2") (pintype "passive"))
      (node (ref "R26") (pin "2") (pinfunction "2_2") (pintype "passive"))
      (node (ref "R27") (pin "1") (pinfunction "1_1") (pintype "passive"))
      (node (ref "R29") (pin "1") (pinfunction "1_1") (pintype "passive"))
    )
    (net (code "49") (name "Net-(R25-Pad2)") (class "Default")
      (node (ref "R25") (pin "2") (pinfunction "2_2") (pintype "passive"))
      (node (ref "R27") (pin "2") (pinfunction "2_2") (pintype "passive"))
      (node (ref "R28") (pin "1") (pinfunction "1_1") (pintype "passive"))
      (node (ref "R30") (pin "1") (pinfunction "1_1") (pintype "passive"))
    )
    (net (code "50") (name "Net-(R29-Pad2)") (class "Default")
      (node (ref "R29") (pin "2") (pinfunction "2_2") (pintype "passive"))
      (node (ref "R31") (pin "2") (pinfunction "2_2") (pintype "passive"))
      (node (ref "R32") (pin "1") (pinfunction "1_1") (pintype "passive"))
      (node (ref "R34") (pin "1") (pinfunction "1_1") (pintype "passive"))
    )
    (net (code "51") (name "Net-(R30-Pad2)") (class "Default")
      (node (ref "R30") (pin "2") (pinfunction "2_2") (pintype "passive"))
      (node (ref "R32") (pin "2") (pinfunction "2_2") (pintype "passive"))
      (node (ref "R33") (pin "1") (pinfunction "1_1") (pintype "passive"))
      (node (ref "R35") (pin "1") (pinfunction "1_1") (pintype "passive"))
    )
    (net (code "52") (name "Net-(R34-Pad2)") (class "Default")
      (node (ref "R34") (pin "2") (pinfunction "2_2") (pintype "passive"))
      (node (ref "R36") (pin "2") (pinfunction "2_2") (pintype "passive"))
      (node (ref "R37") (pin "1") (pinfunction "1_1") (pintype "passive"))
      (node (ref "R39") (pin "1") (pinfunction "1_1") (pintype "passive"))
    )
    (net (code "53") (name "Net-(R35-Pad2)") (class "Default")
      (node (ref "R35") (pin "2") (pinfunction "2_2") (pintype "passive"))
      (node (ref "R37") (pin "2") (pinfunction "2_2") (pintype "passive"))
      (node (ref "R38") (pin "1") (pinfunction "1_1") (pintype "passive"))
      (node (ref "R40") (pin "1") (pinfunction "1_1") (pintype "passive"))
    )
    (net (code "54") (name "Net-(R39-Pad2)") (class "Default")
      (node (ref "R39") (pin "2") (pinfunction "2_2") (pintype "passive"))
      (node (ref "R41") (pin "2") (pinfunction "2_2") (pintype "passive"))
      (node (ref "R42") (pin "1") (pinfunction "1_1") (pintype "passive"))
      (node (ref "R44") (pin "1") (pinfunction "1_1") (pintype "passive"))
    )
    (net (code "55") (name "Net-(R40-Pad2)") (class "Default")
      (node (ref "R40") (pin "2") (pinfunction "2_2") (pintype "passive"))
      (node (ref "R42") (pin "2") (pinfunction "2_2") (pintype "passive"))
      (node (ref "R43") (pin "1") (pinfunction "1_1") (pintype "passive"))
      (node (ref "R45") (pin "1") (pinfunction "1_1") (pintype "passive"))
    )
    (net (code "56") (name "Net-(R44-Pad2)") (class "Default")
      (node (ref "R44") (pin "2") (pinfunction "2_2") (pintype "passive"))
      (node (ref "R47") (pin "2") (pinfunction "2_2") (pintype "passive"))
      (node (ref "R48") (pin "1") (pinfunction "1_1") (pintype "passive"))
      (node (ref "R49") (pin "1") (pinfunction "1_1") (pintype "passive"))
    )
    (net (code "57") (name "Net-(R45-Pad2)") (class "Default")
      (node (ref "R45") (pin "2") (pinfunction "2_2") (pintype "passive"))
      (node (ref "R46") (pin "1") (pinfunction "1_1") (pintype "passive"))
      (node (ref "R48") (pin "2") (pinfunction "2_2") (pintype "passive"))
      (node (ref "R50") (pin "1") (pinfunction "1_1") (pintype "passive"))
    )
    (net (code "58") (name "Net-(R49-Pad2)") (class "Default")
      (node (ref "R49") (pin "2") (pinfunction "2_2") (pintype "passive"))
      (node (ref "R51") (pin "2") (pinfunction "2_2") (pintype "passive"))
      (node (ref "R52") (pin "1") (pinfunction "1_1") (pintype "passive"))
      (node (ref "R54") (pin "1") (pinfunction "1_1") (pintype "passive"))
    )
    (net (code "59") (name "Net-(R50-Pad2)") (class "Default")
      (node (ref "R50") (pin "2") (pinfunction "2_2") (pintype "passive"))
      (node (ref "R52") (pin "2") (pinfunction "2_2") (pintype "passive"))
      (node (ref "R53") (pin "1") (pinfunction "1_1") (pintype "passive"))
      (node (ref "R55") (pin "1") (pinfunction "1_1") (pintype "passive"))
    )
    (net (code "60") (name "Net-(R54-Pad2)") (class "Default")
      (node (ref "R54") (pin "2") (pinfunction "2_2") (pintype "passive"))
      (node (ref "R56") (pin "2") (pinfunction "2_2") (pintype "passive"))
      (node (ref "R57") (pin "1") (pinfunction "1_1") (pintype "passive"))
      (node (ref "R59") (pin "1") (pinfunction "1_1") (pintype "passive"))
    )
    (net (code "61") (name "Net-(R55-Pad2)") (class "Default")
      (node (ref "R55") (pin "2") (pinfunction "2_2") (pintype "passive"))
      (node (ref "R57") (pin "2") (pinfunction "2_2") (pintype "passive"))
      (node (ref "R58") (pin "1") (pinfunction "1_1") (pintype "passive"))
      (node (ref "R60") (pin "1") (pinfunction "1_1") (pintype "passive"))
    )
    (net (code "62") (name "Net-(R59-Pad2)") (class "Default")
      (node (ref "R59") (pin "2") (pinfunction "2_2") (pintype "passive"))
      (node (ref "R61") (pin "2") (pinfunction "2_2") (pintype "passive"))
      (node (ref "R62") (pin "1") (pinfunction "1_1") (pintype "passive"))
      (node (ref "R64") (pin "1") (pinfunction "1_1") (pintype "passive"))
    )
    (net (code "63") (name "Net-(R60-Pad2)") (class "Default")
      (node (ref "R60") (pin "2") (pinfunction "2_2") (pintype "passive"))
      (node (ref "R62") (pin "2") (pinfunction "2_2") (pintype "passive"))
      (node (ref "R63") (pin "1") (pinfunction "1_1") (pintype "passive"))
      (node (ref "R65") (pin "1") (pinfunction "1_1") (pintype "passive"))
    )
    (net (code "64") (name "Net-(R64-Pad2)") (class "Default")
      (node (ref "R64") (pin "2") (pinfunction "2_2") (pintype "passive"))
      (node (ref "R66") (pin "2") (pinfunction "2_2") (pintype "passive"))
      (node (ref "R67") (pin "1") (pinfunction "1_1") (pintype "passive"))
      (node (ref "R69") (pin "1") (pinfunction "1_1") (pintype "passive"))
    )
    (net (code "65") (name "Net-(R65-Pad2)") (class "Default")
      (node (ref "R65") (pin "2") (pinfunction "2_2") (pintype "passive"))
      (node (ref "R67") (pin "2") (pinfunction "2_2") (pintype "passive"))
      (node (ref "R68") (pin "1") (pinfunction "1_1") (pintype "passive"))
      (node (ref "R70") (pin "1") (pinfunction "1_1") (pintype "passive"))
    )
    (net (code "66") (name "Net-(R69-Pad2)") (class "Default")
      (node (ref "R69") (pin "2") (pinfunction "2_2") (pintype "passive"))
      (node (ref "R71") (pin "2") (pinfunction "2_2") (pintype "passive"))
      (node (ref "R72") (pin "1") (pinfunction "1_1") (pintype "passive"))
      (node (ref "R74") (pin "1") (pinfunction "1_1") (pintype "passive"))
    )
    (net (code "67") (name "Net-(R70-Pad2)") (class "Default")
      (node (ref "R70") (pin "2") (pinfunction "2_2") (pintype "passive"))
      (node (ref "R72") (pin "2") (pinfunction "2_2") (pintype "passive"))
      (node (ref "R73") (pin "1") (pinfunction "1_1") (pintype "passive"))
      (node (ref "R75") (pin "1") (pinfunction "1_1") (pintype "passive"))
    )
    (net (code "68") (name "Net-(R74-Pad2)") (class "Default")
      (node (ref "R74") (pin "2") (pinfunction "2_2") (pintype "passive"))
      (node (ref "R76") (pin "2") (pinfunction "2_2") (pintype "passive"))
      (node (ref "R77") (pin "1") (pinfunction "1_1") (pintype "passive"))
      (node (ref "R79") (pin "1") (pinfunction "1_1") (pintype "passive"))
    )
    (net (code "69") (name "Net-(R75-Pad2)") (class "Default")
      (node (ref "R75") (pin "2") (pinfunction "2_2") (pintype "passive"))
      (node (ref "R77") (pin "2") (pinfunction "2_2") (pintype "passive"))
      (node (ref "R78") (pin "1") (pinfunction "1_1") (pintype "passive"))
      (node (ref "R80") (pin "1") (pinfunction "1_1") (pintype "passive"))
    )
    (net (code "70") (name "Net-(R79-Pad2)") (class "Default")
      (node (ref "R79") (pin "2") (pinfunction "2_2") (pintype "passive"))
      (node (ref "R81") (pin "2") (pinfunction "2_2") (pintype "passive"))
      (node (ref "R82") (pin "1") (pinfunction "1_1") (pintype "passive"))
      (node (ref "R84") (pin "1") (pinfunction "1_1") (pintype "passive"))
    )
    (net (code "71") (name "Net-(R80-Pad2)") (class "Default")
      (node (ref "R80") (pin "2") (pinfunction "2_2") (pintype "passive"))
      (node (ref "R82") (pin "2") (pinfunction "2_2") (pintype "passive"))
      (node (ref "R83") (pin "1") (pinfunction "1_1") (pintype "passive"))
      (node (ref "R85") (pin "1") (pinfunction "1_1") (pintype "passive"))
    )
    (net (code "72") (name "Net-(R84-Pad2)") (class "Default")
      (node (ref "R84") (pin "2") (pinfunction "2_2") (pintype "passive"))
      (node (ref "R86") (pin "2") (pinfunction "2_2") (pintype "passive"))
      (node (ref "R87") (pin "1") (pinfunction "1_1") (pintype "passive"))
      (node (ref "R89") (pin "1") (pinfunction "1_1") (pintype "passive"))
    )
    (net (code "73") (name "Net-(R85-Pad2)") (class "Default")
      (node (ref "R85") (pin "2") (pinfunction "2_2") (pintype "passive"))
      (node (ref "R87") (pin "2") (pinfunction "2_2") (pintype "passive"))
      (node (ref "R88") (pin "1") (pinfunction "1_1") (pintype "passive"))
      (node (ref "R90") (pin "1") (pinfunction "1_1") (pintype "passive"))
    )
    (net (code "74") (name "Net-(R89-Pad2)") (class "Default")
      (node (ref "R89") (pin "2") (pinfunction "2_2") (pintype "passive"))
      (node (ref "R91") (pin "2") (pinfunction "2_2") (pintype "passive"))
      (node (ref "R92") (pin "1") (pinfunction "1_1") (pintype "passive"))
      (node (ref "R94") (pin "1") (pinfunction "1_1") (pintype "passive"))
    )
    (net (code "75") (name "Net-(R90-Pad2)") (class "Default")
      (node (ref "R90") (pin "2") (pinfunction "2_2") (pintype "passive"))
      (node (ref "R92") (pin "2") (pinfunction "2_2") (pintype "passive"))
      (node (ref "R93") (pin "1") (pinfunction "1_1") (pintype "passive"))
      (node (ref "R95") (pin "1") (pinfunction "1_1") (pintype "passive"))
    )
    (net (code "76") (name "Net-(R94-Pad2)") (class "Default")
      (node (ref "R94") (pin "2") (pinfunction "2_2") (pintype "passive"))
      (node (ref "R97") (pin "2") (pinfunction "2_2") (pintype "passive"))
      (node (ref "R98") (pin "1") (pinfunction "1_1") (pintype "passive"))
      (node (ref "R99") (pin "1") (pinfunction "1_1") (pintype "passive"))
    )
    (net (code "77") (name "Net-(R100-Pad1)") (class "Default")
      (node (ref "R100") (pin "1") (pinfunction "1_1") (pintype "passive"))
      (node (ref "R95") (pin "2") (pinfunction "2_2") (pintype "passive"))
      (node (ref "R96") (pin "1") (pinfunction "1_1") (pintype "passive"))
      (node (ref "R98") (pin "2") (pinfunction "2_2") (pintype "passive"))
    )
    (net (code "78") (name "Net-(R100-Pad2)") (class "Default")
      (node (ref "R100") (pin "2") (pinfunction "2_2") (pintype "passive"))
      (node (ref "R102") (pin "2") (pinfunction "2_2") (pintype "passive"))
      (node (ref "R103") (pin "1") (pinfunction "1_1") (pintype "passive"))
      (node (ref "R105") (pin "1") (pinfunction "1_1") (pintype "passive"))
    )
    (net (code "79") (name "Net-(R101-Pad2)") (class "Default")
      (node (ref "R101") (pin "2") (pinfunction "2_2") (pintype "passive"))
      (node (ref "R102") (pin "1") (pinfunction "1_1") (pintype "passive"))
      (node (ref "R104") (pin "1") (pinfunction "1_1") (pintype "passive"))
      (node (ref "R99") (pin "2") (pinfunction "2_2") (pintype "passive"))
    )
    (net (code "80") (name "Net-(R104-Pad2)") (class "Default")
      (node (ref "R104") (pin "2") (pinfunction "2_2") (pintype "passive"))
      (node (ref "R106") (pin "2") (pinfunction "2_2") (pintype "passive"))
      (node (ref "R107") (pin "1") (pinfunction "1_1") (pintype "passive"))
      (node (ref "R109") (pin "1") (pinfunction "1_1") (pintype "passive"))
    )
    (net (code "81") (name "Net-(R105-Pad2)") (class "Default")
      (node (ref "R105") (pin "2") (pinfunction "2_2") (pintype "passive"))
      (node (ref "R107") (pin "2") (pinfunction "2_2") (pintype "passive"))
      (node (ref "R108") (pin "1") (pinfunction "1_1") (pintype "passive"))
      (node (ref "R110") (pin "1") (pinfunction "1_1") (pintype "passive"))
    )
    (net (code "82") (name "Net-(R109-Pad2)") (class "Default")
      (node (ref "R109") (pin "2") (pinfunction "2_2") (pintype "passive"))
      (node (ref "R111") (pin "2") (pinfunction "2_2") (pintype "passive"))
      (node (ref "R112") (pin "1") (pinfunction "1_1") (pintype "passive"))
      (node (ref "R114") (pin "1") (pinfunction "1_1") (pintype "passive"))
    )
    (net (code "83") (name "Net-(R110-Pad2)") (class "Default")
      (node (ref "R110") (pin "2") (pinfunction "2_2") (pintype "passive"))
      (node (ref "R112") (pin "2") (pinfunction "2_2") (pintype "passive"))
      (node (ref "R113") (pin "1") (pinfunction "1_1") (pintype "passive"))
      (node (ref "R115") (pin "1") (pinfunction "1_1") (pintype "passive"))
    )
    (net (code "84") (name "Net-(R114-Pad2)") (class "Default")
      (node (ref "R114") (pin "2") (pinfunction "2_2") (pintype "passive"))
      (node (ref "R116") (pin "2") (pinfunction "2_2") (pintype "passive"))
      (node (ref "R117") (pin "1") (pinfunction "1_1") (pintype "passive"))
      (node (ref "R119") (pin "1") (pinfunction "1_1") (pintype "passive"))
    )
    (net (code "85") (name "Net-(R115-Pad2)") (class "Default")
      (node (ref "R115") (pin "2") (pinfunction "2_2") (pintype "passive"))
      (node (ref "R117") (pin "2") (pinfunction "2_2") (pintype "passive"))
      (node (ref "R118") (pin "1") (pinfunction "1_1") (pintype "passive"))
      (node (ref "R120") (pin "1") (pinfunction "1_1") (pintype "passive"))
    )
    (net (code "86") (name "Net-(R119-Pad2)") (class "Default")
      (node (ref "R119") (pin "2") (pinfunction "2_2") (pintype "passive"))
      (node (ref "R121") (pin "2") (pinfunction "2_2") (pintype "passive"))
      (node (ref "R122") (pin "1") (pinfunction "1_1") (pintype "passive"))
      (node (ref "R124") (pin "1") (pinfunction "1_1") (pintype "passive"))
    )
    (net (code "87") (name "Net-(R120-Pad2)") (class "Default")
      (node (ref "R120") (pin "2") (pinfunction "2_2") (pintype "passive"))
      (node (ref "R122") (pin "2") (pinfunction "2_2") (pintype "passive"))
      (node (ref "R123") (pin "1") (pinfunction "1_1") (pintype "passive"))
      (node (ref "R125") (pin "1") (pinfunction "1_1") (pintype "passive"))
    )
    (net (code "88") (name "Net-(R124-Pad2)") (class "Default")
      (node (ref "R124") (pin "2") (pinfunction "2_2") (pintype "passive"))
      (node (ref "R126") (pin "2") (pinfunction "2_2") (pintype "passive"))
      (node (ref "R127") (pin "1") (pinfunction "1_1") (pintype "passive"))
      (node (ref "R129") (pin "1") (pinfunction "1_1") (pintype "passive"))
    )
    (net (code "89") (name "Net-(R125-Pad2)") (class "Default")
      (node (ref "R125") (pin "2") (pinfunction "2_2") (pintype "passive"))
      (node (ref "R127") (pin "2") (pinfunction "2_2") (pintype "passive"))
      (node (ref "R128") (pin "1") (pinfunction "1_1") (pintype "passive"))
      (node (ref "R130") (pin "1") (pinfunction "1_1") (pintype "passive"))
    )
    (net (code "90") (name "Net-(R129-Pad2)") (class "Default")
      (node (ref "R129") (pin "2") (pinfunction "2_2") (pintype "passive"))
      (node (ref "R131") (pin "2") (pinfunction "2_2") (pintype "passive"))
      (node (ref "R132") (pin "1") (pinfunction "1_1") (pintype "passive"))
      (node (ref "R134") (pin "1") (pinfunction "1_1") (pintype "passive"))
    )
    (net (code "91") (name "Net-(R130-Pad2)") (class "Default")
      (node (ref "R130") (pin "2") (pinfunction "2_2") (pintype "passive"))
      (node (ref "R132") (pin "2") (pinfunction "2_2") (pintype "passive"))
      (node (ref "R133") (pin "1") (pinfunction "1_1") (pintype "passive"))
      (node (ref "R135") (pin "1") (pinfunction "1_1") (pintype "passive"))
    )
    (net (code "92") (name "Net-(R134-Pad2)") (class "Default")
      (node (ref "R134") (pin "2") (pinfunction "2_2") (pintype "passive"))
      (node (ref "R136") (pin "2") (pinfunction "2_2") (pintype "passive"))
      (node (ref "R137") (pin "1") (pinfunction "1_1") (pintype "passive"))
      (node (ref "R139") (pin "1") (pinfunction "1_1") (pintype "passive"))
    )
    (net (code "93") (name "Net-(R135-Pad2)") (class "Default")
      (node (ref "R135") (pin "2") (pinfunction "2_2") (pintype "passive"))
      (node (ref "R137") (pin "2") (pinfunction "2_2") (pintype "passive"))
      (node (ref "R138") (pin "1") (pinfunction "1_1") (pintype "passive"))
      (node (ref "R140") (pin "1") (pinfunction "1_1") (pintype "passive"))
    )
    (net (code "94") (name "Net-(R139-Pad2)") (class "Default")
      (node (ref "R139") (pin "2") (pinfunction "2_2") (pintype "passive"))
      (node (ref "R141") (pin "2") (pinfunction "2_2") (pintype "passive"))
      (node (ref "R142") (pin "1") (pinfunction "1_1") (pintype "passive"))
      (node (ref "R144") (pin "1") (pinfunction "1_1") (pintype "passive"))
    )
    (net (code "95") (name "Net-(R140-Pad2)") (class "Default")
      (node (ref "R140") (pin "2") (pinfunction "2_2") (pintype "passive"))
      (node (ref "R142") (pin "2") (pinfunction "2_2") (pintype "passive"))
      (node (ref "R143") (pin "1") (pinfunction "1_1") (pintype "passive"))
      (node (ref "R145") (pin "1") (pinfunction "1_1") (pintype "passive"))
    )
    (net (code "96") (name "Net-(R144-Pad2)") (class "Default")
      (node (ref "R144") (pin "2") (pinfunction "2_2") (pintype "passive"))
      (node (ref "R147") (pin "2") (pinfunction "2_2") (pintype "passive"))
      (node (ref "R148") (pin "1") (pinfunction "1_1") (pintype "passive"))
      (node (ref "R149") (pin "1") (pinfunction "1_1") (pintype "passive"))
    )
    (net (code "97") (name "Net-(R145-Pad2)") (class "Default")
      (node (ref "R145") (pin "2") (pinfunction "2_2") (pintype "passive"))
      (node (ref "R146") (pin "1") (pinfunction "1_1") (pintype "passive"))
      (node (ref "R148") (pin "2") (pinfunction "2_2") (pintype "passive"))
      (node (ref "R150") (pin "1") (pinfunction "1_1") (pintype "passive"))
    )
    (net (code "98") (name "Net-(R149-Pad2)") (class "Default")
      (node (ref "R149") (pin "2") (pinfunction "2_2") (pintype "passive"))
      (node (ref "R151") (pin "2") (pinfunction "2_2") (pintype "passive"))
      (node (ref "R152") (pin "1") (pinfunction "1_1") (pintype "passive"))
      (node (ref "R154") (pin "1") (pinfunction "1_1") (pintype "passive"))
    )
    (net (code "99") (name "Net-(R150-Pad2)") (class "Default")
      (node (ref "R150") (pin "2") (pinfunction "2_2") (pintype "passive"))
      (node (ref "R152") (pin "2") (pinfunction "2_2") (pintype "passive"))
      (node (ref "R153") (pin "1") (pinfunction "1_1") (pintype "passive"))
      (node (ref "R155") (pin "1") (pinfunction "1_1") (pintype "passive"))
    )
    (net (code "100") (name "Net-(R154-Pad2)") (class "Default")
      (node (ref "R154") (pin "2") (pinfunction "2_2") (pintype "passive"))
      (node (ref "R156") (pin "2") (pinfunction "2_2") (pintype "passive"))
      (node (ref "R157") (pin "1") (pinfunction "1_1") (pintype "passive"))
      (node (ref "R159") (pin "1") (pinfunction "1_1") (pintype "passive"))
    )
    (net (code "101") (name "Net-(R155-Pad2)") (class "Default")
      (node (ref "R155") (pin "2") (pinfunction "2_2") (pintype "passive"))
      (node (ref "R157") (pin "2") (pinfunction "2_2") (pintype "passive"))
      (node (ref "R158") (pin "1") (pinfunction "1_1") (pintype "passive"))
      (node (ref "R160") (pin "1") (pinfunction "1_1") (pintype "passive"))
    )
    (net (code "102") (name "Net-(R160-Pad2)") (class "Default")
      (node (ref "R160") (pin "2") (pinfunction "2_2") (pintype "passive"))
      (node (ref "R2") (pin "2") (pinfunction "2_2") (pintype "passive"))
      (node (ref "R3") (pin "1") (pinfunction "1_1") (pintype "passive"))
      (node (ref "R5") (pin "1") (pinfunction "1_1") (pintype "passive"))
    )
    (net (code "103") (name "unconnected-(X1-PadG1)") (class "Default")
      (node (ref "X1") (pin "G1") (pinfunction "G1_G1") (pintype "passive"))
    )
    (net (code "104") (name "unconnected-(X1-PadG2)") (class "Default")
      (node (ref "X1") (pin "G2") (pinfunction "G2_G2") (pintype "passive"))
    )
  )
)
